# 04_-_CPU_-_POWER.net
KiCad netlist of a schematic drawn in Altium Designer
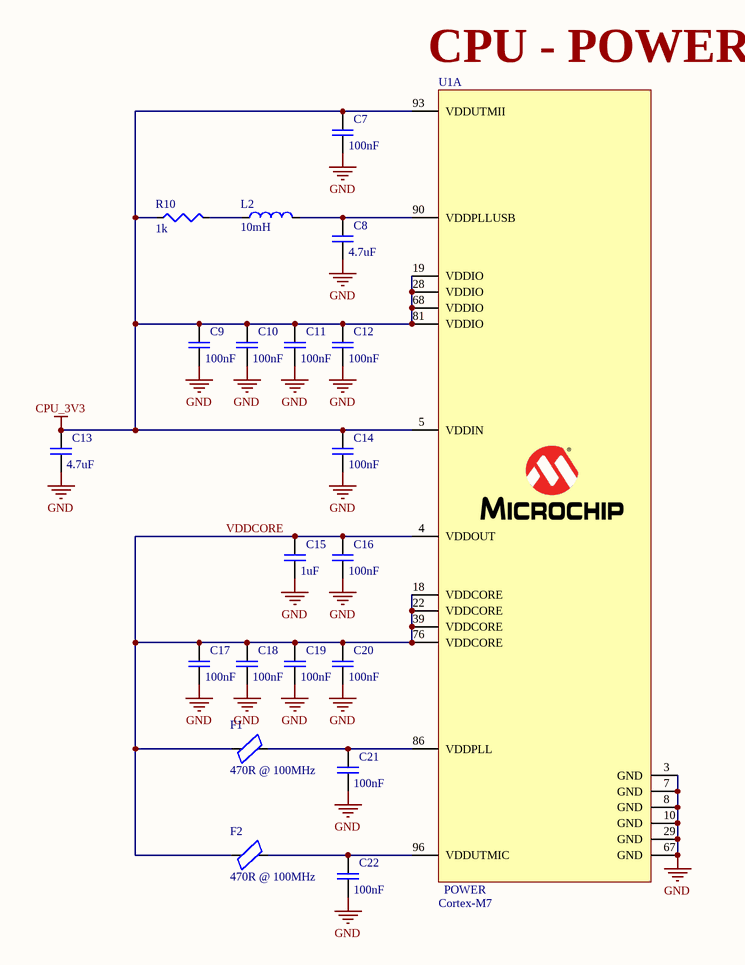
[diagram p0: [04] - CPU - POWER.SchDoc]

(export (version "E")
  (design (tool "Eeschema 10.0.6"))
  (components
    (comp (ref "C7")
      (value "100nF")
      (footprint "C0603")
      (description "C0603")
      (fields (field (name "Comment") "02016D104KAT2A"))
      (libsource (lib "Passive components") (part "02016D104KAT2A"))
    )
    (comp (ref "C8")
      (value "4.7uF")
      (footprint "C0603")
      (description "C0603")
      (fields (field (name "Comment") "02016D104KAT2A"))
      (libsource (lib "Passive components") (part "02016D104KAT2A"))
    )
    (comp (ref "C9")
      (value "100nF")
      (footprint "C0603")
      (description "C0603")
      (fields (field (name "Comment") "02016D104KAT2A"))
      (libsource (lib "Passive components") (part "02016D104KAT2A"))
    )
    (comp (ref "C10")
      (value "100nF")
      (footprint "C0603")
      (description "C0603")
      (fields (field (name "Comment") "02016D104KAT2A"))
      (libsource (lib "Passive components") (part "02016D104KAT2A"))
    )
    (comp (ref "C11")
      (value "100nF")
      (footprint "C0603")
      (description "C0603")
      (fields (field (name "Comment") "02016D104KAT2A"))
      (libsource (lib "Passive components") (part "02016D104KAT2A"))
    )
    (comp (ref "C12")
      (value "100nF")
      (footprint "C0603")
      (description "C0603")
      (fields (field (name "Comment") "02016D104KAT2A"))
      (libsource (lib "Passive components") (part "02016D104KAT2A"))
    )
    (comp (ref "C13")
      (value "4.7uF")
      (footprint "C0603")
      (description "C0603")
      (fields (field (name "Comment") "02016D104KAT2A"))
      (libsource (lib "Passive components") (part "02016D104KAT2A"))
    )
    (comp (ref "C14")
      (value "100nF")
      (footprint "C0603")
      (description "C0603")
      (fields (field (name "Comment") "02016D104KAT2A"))
      (libsource (lib "Passive components") (part "02016D104KAT2A"))
    )
    (comp (ref "C15")
      (value "1uF")
      (footprint "C0603")
      (description "C0603")
      (fields (field (name "Comment") "02016D104KAT2A"))
      (libsource (lib "Passive components") (part "02016D104KAT2A"))
    )
    (comp (ref "C16")
      (value "100nF")
      (footprint "C0603")
      (description "C0603")
      (fields (field (name "Comment") "02016D104KAT2A"))
      (libsource (lib "Passive components") (part "02016D104KAT2A"))
    )
    (comp (ref "C17")
      (value "100nF")
      (footprint "C0603")
      (description "C0603")
      (fields (field (name "Comment") "02016D104KAT2A"))
      (libsource (lib "Passive components") (part "02016D104KAT2A"))
    )
    (comp (ref "C18")
      (value "100nF")
      (footprint "C0603")
      (description "C0603")
      (fields (field (name "Comment") "02016D104KAT2A"))
      (libsource (lib "Passive components") (part "02016D104KAT2A"))
    )
    (comp (ref "C19")
      (value "100nF")
      (footprint "C0603")
      (description "C0603")
      (fields (field (name "Comment") "02016D104KAT2A"))
      (libsource (lib "Passive components") (part "02016D104KAT2A"))
    )
    (comp (ref "C20")
      (value "100nF")
      (footprint "C0603")
      (description "C0603")
      (fields (field (name "Comment") "02016D104KAT2A"))
      (libsource (lib "Passive components") (part "02016D104KAT2A"))
    )
    (comp (ref "C21")
      (value "100nF")
      (footprint "C0603")
      (description "C0603")
      (fields (field (name "Comment") "02016D104KAT2A"))
      (libsource (lib "Passive components") (part "02016D104KAT2A"))
    )
    (comp (ref "C22")
      (value "100nF")
      (footprint "C0603")
      (description "C0603")
      (fields (field (name "Comment") "02016D104KAT2A"))
      (libsource (lib "Passive components") (part "02016D104KAT2A"))
    )
    (comp (ref "F1")
      (value "470R @ 100MHz")
      (footprint "Ferrite bead 0603")
      (description "Ferrite bead 0603")
      (fields (field (name "Comment") "BLM18AG121SN1D"))
      (libsource (lib "Passive components") (part "BLM18AG121SN1D"))
    )
    (comp (ref "F2")
      (value "470R @ 100MHz")
      (footprint "Ferrite bead 0603")
      (description "Ferrite bead 0603")
      (fields (field (name "Comment") "BLM18AG121SN1D"))
      (libsource (lib "Passive components") (part "BLM18AG121SN1D"))
    )
    (comp (ref "L2")
      (value "10mH")
      (footprint "Inductor 0603")
      (description "Inductor 0603")
      (fields (field (name "Comment") "MLZ1608A2R2WT"))
      (libsource (lib "Passive components") (part "MLZ1608A2R2WT"))
    )
    (comp (ref "R10")
      (value "1k")
      (footprint "R0603")
      (description "R0603")
      (fields (field (name "Comment") "CPF-A-0603B100KE1"))
      (libsource (lib "Passive components") (part "CPF-A-0603B100KE1"))
    )
    (comp (ref "U1")
      (value "Cortex-M7")
      (footprint "ATSAMS70N19A-AN")
      (description "ATSAMS70N19")
      (libsource (lib "Microcontrollers") (part "ATSAMS70N19A-AN"))
    )
  )
  (nets
    (net (code "1") (name "/VDDCORE") (class "Default")
      (node (ref "C15") (pin "2") (pinfunction "2_2") (pintype "passive"))
      (node (ref "C16") (pin "2") (pinfunction "2_2") (pintype "passive"))
      (node (ref "C17") (pin "2") (pinfunction "2_2") (pintype "passive"))
      (node (ref "C18") (pin "2") (pinfunction "2_2") (pintype "passive"))
      (node (ref "C19") (pin "2") (pinfunction "2_2") (pintype "passive"))
      (node (ref "C20") (pin "2") (pinfunction "2_2") (pintype "passive"))
      (node (ref "F1") (pin "1") (pinfunction "1_1") (pintype "passive"))
      (node (ref "F2") (pin "1") (pinfunction "1_1") (pintype "passive"))
      (node (ref "U1") (pin "18") (pinfunction "VDDCORE_18") (pintype "passive"))
      (node (ref "U1") (pin "22") (pinfunction "VDDCORE_22") (pintype "passive"))
      (node (ref "U1") (pin "39") (pinfunction "VDDCORE_39") (pintype "passive"))
      (node (ref "U1") (pin "4") (pinfunction "VDDOUT_4") (pintype "passive"))
      (node (ref "U1") (pin "76") (pinfunction "VDDCORE_76") (pintype "passive"))
    )
    (net (code "2") (name "CPU_3V3") (class "Default")
      (node (ref "C10") (pin "2") (pinfunction "2_2") (pintype "passive"))
      (node (ref "C11") (pin "2") (pinfunction "2_2") (pintype "passive"))
      (node (ref "C12") (pin "2") (pinfunction "2_2") (pintype "passive"))
      (node (ref "C13") (pin "2") (pinfunction "2_2") (pintype "passive"))
      (node (ref "C14") (pin "2") (pinfunction "2_2") (pintype "passive"))
      (node (ref "C7") (pin "2") (pinfunction "2_2") (pintype "passive"))
      (node (ref "C9") (pin "2") (pinfunction "2_2") (pintype "passive"))
      (node (ref "R10") (pin "1") (pinfunction "1_1") (pintype "passive"))
      (node (ref "U1") (pin "19") (pinfunction "VDDIO_19") (pintype "passive"))
      (node (ref "U1") (pin "28") (pinfunction "VDDIO_28") (pintype "passive"))
      (node (ref "U1") (pin "5") (pinfunction "VDDIN_5") (pintype "passive"))
      (node (ref "U1") (pin "68") (pinfunction "VDDIO_68") (pintype "passive"))
      (node (ref "U1") (pin "81") (pinfunction "VDDIO_81") (pintype "passive"))
      (node (ref "U1") (pin "93") (pinfunction "VDDUTMII_93") (pintype "passive"))
    )
    (net (code "3") (name "GND") (class "Default")
      (node (ref "C10") (pin "1") (pinfunction "1_1") (pintype "passive"))
      (node (ref "C11") (pin "1") (pinfunction "1_1") (pintype "passive"))
      (node (ref "C12") (pin "1") (pinfunction "1_1") (pintype "passive"))
      (node (ref "C13") (pin "1") (pinfunction "1_1") (pintype "passive"))
      (node (ref "C14") (pin "1") (pinfunction "1_1") (pintype "passive"))
      (node (ref "C15") (pin "1") (pinfunction "1_1") (pintype "passive"))
      (node (ref "C16") (pin "1") (pinfunction "1_1") (pintype "passive"))
      (node (ref "C17") (pin "1") (pinfunction "1_1") (pintype "passive"))
      (node (ref "C18") (pin "1") (pinfunction "1_1") (pintype "passive"))
      (node (ref "C19") (pin "1") (pinfunction "1_1") (pintype "passive"))
      (node (ref "C20") (pin "1") (pinfunction "1_1") (pintype "passive"))
      (node (ref "C21") (pin "1") (pinfunction "1_1") (pintype "passive"))
      (node (ref "C22") (pin "1") (pinfunction "1_1") (pintype "passive"))
      (node (ref "C7") (pin "1") (pinfunction "1_1") (pintype "passive"))
      (node (ref "C8") (pin "1") (pinfunction "1_1") (pintype "passive"))
      (node (ref "C9") (pin "1") (pinfunction "1_1") (pintype "passive"))
      (node (ref "U1") (pin "10") (pinfunction "GND_10") (pintype "passive"))
      (node (ref "U1") (pin "29") (pinfunction "GND_29") (pintype "passive"))
      (node (ref "U1") (pin "3") (pinfunction "GND_3") (pintype "passive"))
      (node (ref "U1") (pin "67") (pinfunction "GND_67") (pintype "passive"))
      (node (ref "U1") (pin "7") (pinfunction "GND_7") (pintype "passive"))
      (node (ref "U1") (pin "8") (pinfunction "GND_8") (pintype "passive"))
    )
    (net (code "4") (name "Net-(L2-Pad1)") (class "Default")
      (node (ref "L2") (pin "1") (pinfunction "1_1") (pintype "passive"))
      (node (ref "R10") (pin "2") (pinfunction "2_2") (pintype "passive"))
    )
    (net (code "5") (name "Net-(U1A-VDDPLL)") (class "Default")
      (node (ref "C21") (pin "2") (pinfunction "2_2") (pintype "passive"))
      (node (ref "F1") (pin "2") (pinfunction "2_2") (pintype "passive"))
      (node (ref "U1") (pin "86") (pinfunction "VDDPLL_86") (pintype "passive"))
    )
    (net (code "6") (name "Net-(U1A-VDDPLLUSB)") (class "Default")
      (node (ref "C8") (pin "2") (pinfunction "2_2") (pintype "passive"))
      (node (ref "L2") (pin "2") (pinfunction "2_2") (pintype "passive"))
      (node (ref "U1") (pin "90") (pinfunction "VDDPLLUSB_90") (pintype "passive"))
    )
    (net (code "7") (name "Net-(U1A-VDDUTMIC)") (class "Default")
      (node (ref "C22") (pin "2") (pinfunction "2_2") (pintype "passive"))
      (node (ref "F2") (pin "2") (pinfunction "2_2") (pintype "passive"))
      (node (ref "U1") (pin "96") (pinfunction "VDDUTMIC_96") (pintype "passive"))
    )
  )
)
